# MagicWand_Schematic.net
KiCad netlist of a schematic drawn in Altium Designer
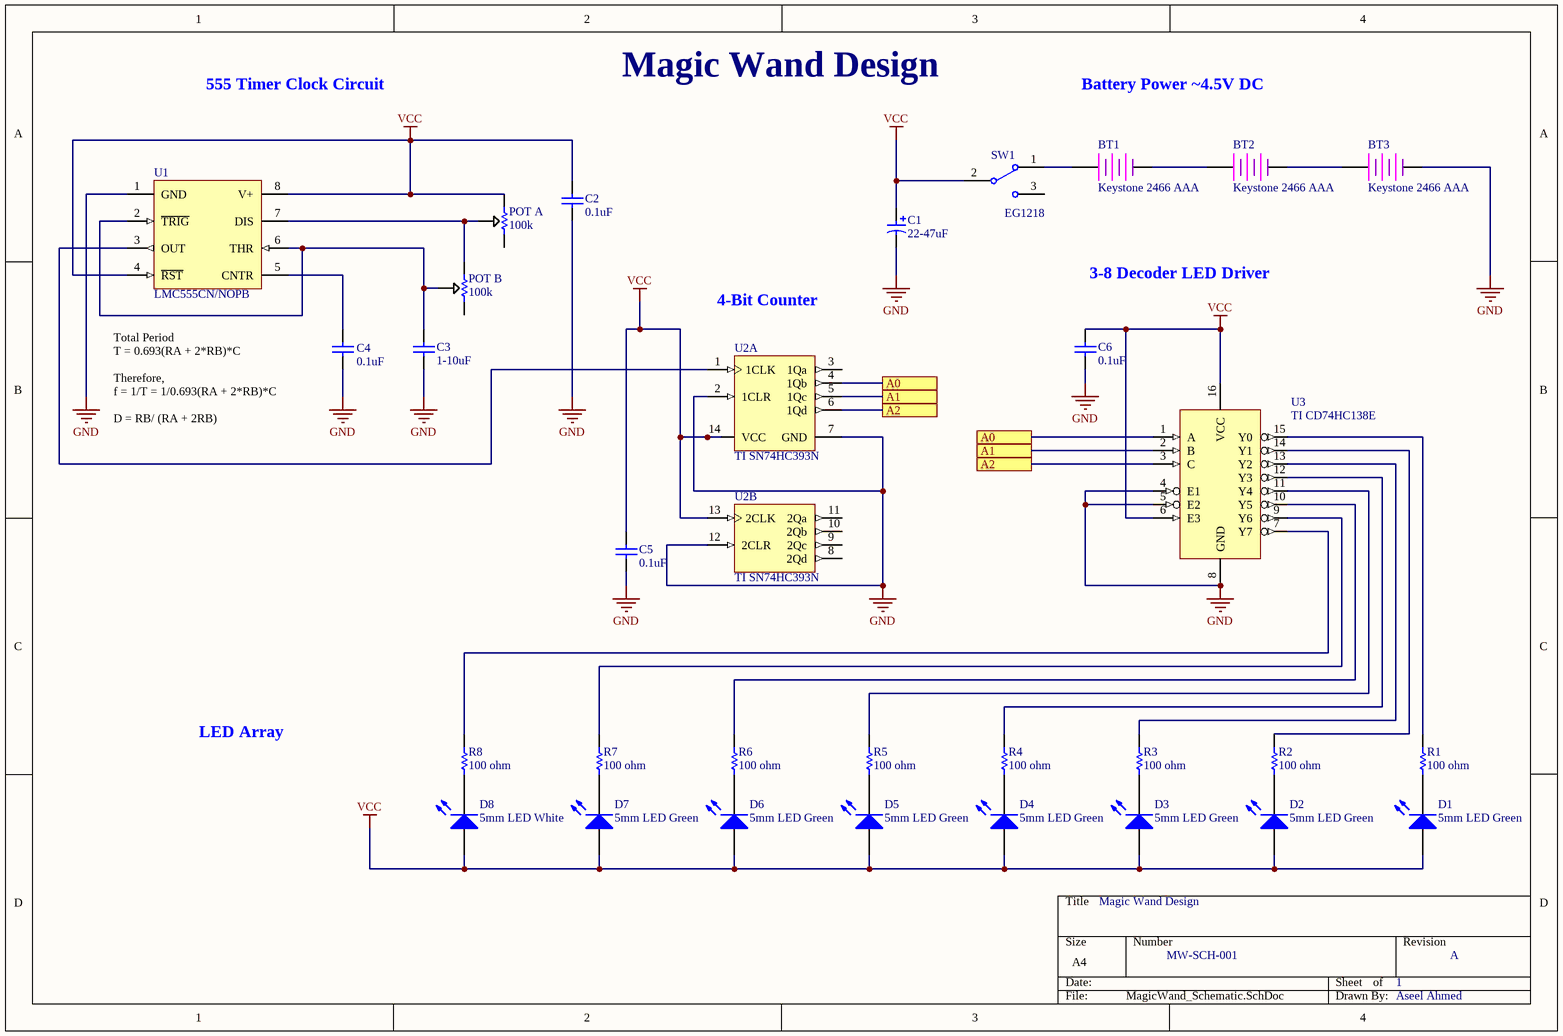
[diagram p0: MagicWand_Schematic.SchDoc]

(export (version "E")
  (design (tool "Eeschema 10.0.6"))
  (components
    (comp (ref "BT1")
      (value "Keystone 2466 AAA")
      (footprint "PCB-2466")
      (description "Battery holder, AAA, 1 cell, PC mount")
      (fields (field (name "MANUFACTURER PART NUMBER") "2466"))
      (libsource (lib "My Personal Space") (part "SYM-2466"))
    )
    (comp (ref "BT2")
      (value "Keystone 2466 AAA")
      (footprint "PCB-2466")
      (description "Battery holder, AAA, 1 cell, PC mount")
      (fields (field (name "MANUFACTURER PART NUMBER") "2466"))
      (libsource (lib "My Personal Space") (part "SYM-2466"))
    )
    (comp (ref "BT3")
      (value "Keystone 2466 AAA")
      (footprint "PCB-2466")
      (description "Battery holder, AAA, 1 cell, PC mount")
      (fields (field (name "MANUFACTURER PART NUMBER") "2466"))
      (libsource (lib "My Personal Space") (part "SYM-2466"))
    )
    (comp (ref "C1")
      (value "22-47uF")
      (footprint "PCB-xswzn1jk2ejoevwvaoxh-1")
      (description "Electrolytic capacitor Radial lead 2.5 mm 10 µF 16 V 20 % (Ø) 4 mm Panasonic EEA-GA1C100H 1 pc(s)")
      (libsource (lib "My Personal Space") (part "SYM-b868704b0d3c67af-1"))
    )
    (comp (ref "C2")
      (value "0.1uF")
      (footprint "PCB-ql28fbuo3tond8refhb5-1")
      (description "K 100nF Ceramic Multilayer Capacitor, 50 V dc, +125degC, X7R Dielectric, +/-10%")
      (libsource (lib "My Personal Space") (part "SYM-1272d9258f2acdb5-2"))
    )
    (comp (ref "C3")
      (value "1-10uF")
      (footprint "PCB-ql28fbuo3tond8refhb5-1")
      (description "K 100nF Ceramic Multilayer Capacitor, 50 V dc, +125degC, X7R Dielectric, +/-10%")
      (libsource (lib "My Personal Space") (part "SYM-1272d9258f2acdb5-2"))
    )
    (comp (ref "C4")
      (value "0.1uF")
      (footprint "PCB-ql28fbuo3tond8refhb5-1")
      (description "K 100nF Ceramic Multilayer Capacitor, 50 V dc, +125degC, X7R Dielectric, +/-10%")
      (libsource (lib "My Personal Space") (part "SYM-1272d9258f2acdb5-2"))
    )
    (comp (ref "C5")
      (value "0.1uF")
      (footprint "PCB-ql28fbuo3tond8refhb5-1")
      (description "K 100nF Ceramic Multilayer Capacitor, 50 V dc, +125degC, X7R Dielectric, +/-10%")
      (libsource (lib "My Personal Space") (part "SYM-1272d9258f2acdb5-2"))
    )
    (comp (ref "C6")
      (value "0.1uF")
      (footprint "PCB-ql28fbuo3tond8refhb5-1")
      (description "K 100nF Ceramic Multilayer Capacitor, 50 V dc, +125degC, X7R Dielectric, +/-10%")
      (libsource (lib "My Personal Space") (part "SYM-1272d9258f2acdb5-2"))
    )
    (comp (ref "D1")
      (value "5mm LED Green")
      (footprint "PCB-6hmn14p3euwrtpae4j9f-1")
      (description "Green 5 mm 60° Diffused 30 mcd 2.2 V Through Hole LED - T-1¾")
      (fields (field (name "MANUFACTURER PART NUMBER") "SSL-LX5093PGD"))
      (libsource (lib "My Personal Space") (part "SYM-4a898382afec954e-1"))
    )
    (comp (ref "D2")
      (value "5mm LED Green")
      (footprint "PCB-6hmn14p3euwrtpae4j9f-1")
      (description "Green 5 mm 60° Diffused 30 mcd 2.2 V Through Hole LED - T-1¾")
      (fields (field (name "MANUFACTURER PART NUMBER") "SSL-LX5093PGD"))
      (libsource (lib "My Personal Space") (part "SYM-4a898382afec954e-1"))
    )
    (comp (ref "D3")
      (value "5mm LED Green")
      (footprint "PCB-6hmn14p3euwrtpae4j9f-1")
      (description "Green 5 mm 60° Diffused 30 mcd 2.2 V Through Hole LED - T-1¾")
      (fields (field (name "MANUFACTURER PART NUMBER") "SSL-LX5093PGD"))
      (libsource (lib "My Personal Space") (part "SYM-4a898382afec954e-1"))
    )
    (comp (ref "D4")
      (value "5mm LED Green")
      (footprint "PCB-6hmn14p3euwrtpae4j9f-1")
      (description "Green 5 mm 60° Diffused 30 mcd 2.2 V Through Hole LED - T-1¾")
      (fields (field (name "MANUFACTURER PART NUMBER") "SSL-LX5093PGD"))
      (libsource (lib "My Personal Space") (part "SYM-4a898382afec954e-1"))
    )
    (comp (ref "D5")
      (value "5mm LED Green")
      (footprint "PCB-6hmn14p3euwrtpae4j9f-1")
      (description "Green 5 mm 60° Diffused 30 mcd 2.2 V Through Hole LED - T-1¾")
      (fields (field (name "MANUFACTURER PART NUMBER") "SSL-LX5093PGD"))
      (libsource (lib "My Personal Space") (part "SYM-4a898382afec954e-1"))
    )
    (comp (ref "D6")
      (value "5mm LED Green")
      (footprint "PCB-6hmn14p3euwrtpae4j9f-1")
      (description "Green 5 mm 60° Diffused 30 mcd 2.2 V Through Hole LED - T-1¾")
      (fields (field (name "MANUFACTURER PART NUMBER") "SSL-LX5093PGD"))
      (libsource (lib "My Personal Space") (part "SYM-4a898382afec954e-1"))
    )
    (comp (ref "D7")
      (value "5mm LED Green")
      (footprint "PCB-6hmn14p3euwrtpae4j9f-1")
      (description "Green 5 mm 60° Diffused 30 mcd 2.2 V Through Hole LED - T-1¾")
      (fields (field (name "MANUFACTURER PART NUMBER") "SSL-LX5093PGD"))
      (libsource (lib "My Personal Space") (part "SYM-4a898382afec954e-1"))
    )
    (comp (ref "D8")
      (value "5mm LED White")
      (footprint "PCB-6hmn14p3euwrtpae4j9f-1")
      (description "Green 5 mm 60° Diffused 30 mcd 2.2 V Through Hole LED - T-1¾")
      (fields (field (name "MANUFACTURER PART NUMBER") "SSL-LX5093PGD"))
      (libsource (lib "My Personal Space") (part "SYM-4a898382afec954e-1"))
    )
    (comp (ref "POT A")
      (value "100k")
      (footprint "PCB-1580288-1")
      (description "Res Cermet Trimmer 10K Ohm 10% 1/2W 1(Elec)/1(Mech)Turn 2.6mm (7 X 7 X 5.8mm) Pin Thru-Hole Bulk")
      (fields (field (name "MANUFACTURER PART NUMBER") "CT6EP103"))
      (libsource (lib "My Personal Space") (part "SYM-32ccf8683850ed0b-1"))
    )
    (comp (ref "POT B")
      (value "100k")
      (footprint "PCB-1580288-1")
      (description "Res Cermet Trimmer 10K Ohm 10% 1/2W 1(Elec)/1(Mech)Turn 2.6mm (7 X 7 X 5.8mm) Pin Thru-Hole Bulk")
      (fields (field (name "MANUFACTURER PART NUMBER") "CT6EP103"))
      (libsource (lib "My Personal Space") (part "SYM-32ccf8683850ed0b-1"))
    )
    (comp (ref "R1")
      (value "100 ohm")
      (footprint "PCB-0jk5y5qyb1smy9vf6b7t-1")
      (description "Res, 10K, 250mW, 5%, Axial")
      (libsource (lib "My Personal Space") (part "SYM-db3e1311f37e04f9-4"))
    )
    (comp (ref "R2")
      (value "100 ohm")
      (footprint "PCB-0jk5y5qyb1smy9vf6b7t-1")
      (description "Res, 10K, 250mW, 5%, Axial")
      (libsource (lib "My Personal Space") (part "SYM-db3e1311f37e04f9-4"))
    )
    (comp (ref "R3")
      (value "100 ohm")
      (footprint "PCB-0jk5y5qyb1smy9vf6b7t-1")
      (description "Res, 10K, 250mW, 5%, Axial")
      (libsource (lib "My Personal Space") (part "SYM-db3e1311f37e04f9-4"))
    )
    (comp (ref "R4")
      (value "100 ohm")
      (footprint "PCB-0jk5y5qyb1smy9vf6b7t-1")
      (description "Res, 10K, 250mW, 5%, Axial")
      (libsource (lib "My Personal Space") (part "SYM-db3e1311f37e04f9-4"))
    )
    (comp (ref "R5")
      (value "100 ohm")
      (footprint "PCB-0jk5y5qyb1smy9vf6b7t-1")
      (description "Res, 10K, 250mW, 5%, Axial")
      (libsource (lib "My Personal Space") (part "SYM-db3e1311f37e04f9-4"))
    )
    (comp (ref "R6")
      (value "100 ohm")
      (footprint "PCB-0jk5y5qyb1smy9vf6b7t-1")
      (description "Res, 10K, 250mW, 5%, Axial")
      (libsource (lib "My Personal Space") (part "SYM-db3e1311f37e04f9-4"))
    )
    (comp (ref "R7")
      (value "100 ohm")
      (footprint "PCB-0jk5y5qyb1smy9vf6b7t-1")
      (description "Res, 10K, 250mW, 5%, Axial")
      (libsource (lib "My Personal Space") (part "SYM-db3e1311f37e04f9-4"))
    )
    (comp (ref "R8")
      (value "100 ohm")
      (footprint "PCB-0jk5y5qyb1smy9vf6b7t-1")
      (description "Res, 10K, 250mW, 5%, Axial")
      (libsource (lib "My Personal Space") (part "SYM-db3e1311f37e04f9-4"))
    )
    (comp (ref "SW1")
      (value "EG1218")
      (footprint "ESWI-EG1218_V")
      (description "Slide Switch, 500 V, -20 to 70 degC, 3-Pin THD, RoHS")
      (libsource (lib "My Personal Space") (part "SW-SPDT-3"))
    )
    (comp (ref "U1")
      (value "LMC555CN/NOPB")
      (footprint "N08E")
      (description "CMOS Timer, 8-pin MDIP, Pb-Free")
      (libsource (lib "My Personal Space") (part "AN-TIMER-LMC555-8"))
    )
    (comp (ref "U2")
      (value "TI SN74HC393N")
      (footprint "PCB-te1ukpb7ypv15gwynu8x-1")
      (description "Texas Instruments - SN74HC393N - Counter/Divider Dual 4-Bit Binary UP 14-Pin PDIP Tube")
      (fields (field (name "MANUFACTURER PART NUMBER") "SN74HC393N"))
      (libsource (lib "My Personal Space") (part "SYM-3c53f5596157e394-2"))
    )
    (comp (ref "U3")
      (value "TI CD74HC138E")
      (footprint "PCB-iqyivjlmuk83cucpld0n-1")
      (description "TEXAS INSTRUMENTS   CD74HC138E   Logic Type:Decoder / Demultiplexer")
      (fields
        (field (name "MANUFACTURER") "Texas Instruments")
        (field (name "MANUFACTURER PART NUMBER") "CD74HC138E")
      )
      (libsource (lib "My Personal Space") (part "SYM-1166716-1"))
    )
  )
  (nets
    (net (code "1") (name "/A0") (class "Default")
      (node (ref "U2") (pin "4") (pinfunction "1Qb_4") (pintype "output"))
      (node (ref "U3") (pin "1") (pinfunction "A_1") (pintype "input"))
    )
    (net (code "2") (name "/A1") (class "Default")
      (node (ref "U2") (pin "5") (pinfunction "1Qc_5") (pintype "output"))
      (node (ref "U3") (pin "2") (pinfunction "B_2") (pintype "input"))
    )
    (net (code "3") (name "/A2") (class "Default")
      (node (ref "U2") (pin "6") (pinfunction "1Qd_6") (pintype "output"))
      (node (ref "U3") (pin "3") (pinfunction "C_3") (pintype "input"))
    )
    (net (code "4") (name "GND") (class "Default")
      (node (ref "BT3") (pin "2") (pinfunction "-_2") (pintype "passive"))
      (node (ref "C1") (pin "2") (pinfunction "2_2") (pintype "passive"))
      (node (ref "C2") (pin "1") (pinfunction "1_1") (pintype "passive"))
      (node (ref "C3") (pin "1") (pinfunction "1_1") (pintype "passive"))
      (node (ref "C4") (pin "1") (pinfunction "1_1") (pintype "passive"))
      (node (ref "C5") (pin "1") (pinfunction "1_1") (pintype "passive"))
      (node (ref "C6") (pin "1") (pinfunction "1_1") (pintype "passive"))
      (node (ref "U1") (pin "1") (pinfunction "GND_1") (pintype "power_in"))
      (node (ref "U2") (pin "12") (pinfunction "2CLR_12") (pintype "input"))
      (node (ref "U2") (pin "2") (pinfunction "1CLR_2") (pintype "input"))
      (node (ref "U2") (pin "7") (pinfunction "GND_7") (pintype "power_in"))
      (node (ref "U3") (pin "4") (pinfunction "E1_4") (pintype "input"))
      (node (ref "U3") (pin "5") (pinfunction "E2_5") (pintype "input"))
      (node (ref "U3") (pin "8") (pinfunction "GND_8") (pintype "power_in"))
    )
    (net (code "5") (name "Net-(BT1-+)") (class "Default")
      (node (ref "BT1") (pin "1") (pinfunction "+_1") (pintype "passive"))
      (node (ref "SW1") (pin "1") (pinfunction "1_1") (pintype "passive"))
    )
    (net (code "6") (name "Net-(BT1--)") (class "Default")
      (node (ref "BT1") (pin "2") (pinfunction "-_2") (pintype "passive"))
      (node (ref "BT2") (pin "1") (pinfunction "+_1") (pintype "passive"))
    )
    (net (code "7") (name "Net-(BT2--)") (class "Default")
      (node (ref "BT2") (pin "2") (pinfunction "-_2") (pintype "passive"))
      (node (ref "BT3") (pin "1") (pinfunction "+_1") (pintype "passive"))
    )
    (net (code "8") (name "Net-(D1-K)") (class "Default")
      (node (ref "D1") (pin "2") (pinfunction "K_2") (pintype "passive"))
      (node (ref "R1") (pin "1") (pinfunction "1_1") (pintype "passive"))
    )
    (net (code "9") (name "Net-(D2-K)") (class "Default")
      (node (ref "D2") (pin "2") (pinfunction "K_2") (pintype "passive"))
      (node (ref "R2") (pin "1") (pinfunction "1_1") (pintype "passive"))
    )
    (net (code "10") (name "Net-(D3-K)") (class "Default")
      (node (ref "D3") (pin "2") (pinfunction "K_2") (pintype "passive"))
      (node (ref "R3") (pin "1") (pinfunction "1_1") (pintype "passive"))
    )
    (net (code "11") (name "Net-(D4-K)") (class "Default")
      (node (ref "D4") (pin "2") (pinfunction "K_2") (pintype "passive"))
      (node (ref "R4") (pin "1") (pinfunction "1_1") (pintype "passive"))
    )
    (net (code "12") (name "Net-(D5-K)") (class "Default")
      (node (ref "D5") (pin "2") (pinfunction "K_2") (pintype "passive"))
      (node (ref "R5") (pin "1") (pinfunction "1_1") (pintype "passive"))
    )
    (net (code "13") (name "Net-(D6-K)") (class "Default")
      (node (ref "D6") (pin "2") (pinfunction "K_2") (pintype "passive"))
      (node (ref "R6") (pin "1") (pinfunction "1_1") (pintype "passive"))
    )
    (net (code "14") (name "Net-(D7-K)") (class "Default")
      (node (ref "D7") (pin "2") (pinfunction "K_2") (pintype "passive"))
      (node (ref "R7") (pin "1") (pinfunction "1_1") (pintype "passive"))
    )
    (net (code "15") (name "Net-(D8-K)") (class "Default")
      (node (ref "D8") (pin "2") (pinfunction "K_2") (pintype "passive"))
      (node (ref "R8") (pin "1") (pinfunction "1_1") (pintype "passive"))
    )
    (net (code "16") (name "Net-(U1-CNTR)") (class "Default")
      (node (ref "C4") (pin "2") (pinfunction "2_2") (pintype "passive"))
      (node (ref "U1") (pin "5") (pinfunction "CNTR_5") (pintype "passive"))
    )
    (net (code "17") (name "Net-(U1-DIS)") (class "Default")
      (node (ref "POT A") (pin "3") (pinfunction "3_3") (pintype "passive"))
      (node (ref "POT B") (pin "2") (pinfunction "2_2") (pintype "passive"))
      (node (ref "U1") (pin "7") (pinfunction "DIS_7") (pintype "open_collector"))
    )
    (net (code "18") (name "Net-(U1-OUT)") (class "Default")
      (node (ref "U1") (pin "3") (pinfunction "OUT_3") (pintype "output"))
      (node (ref "U2") (pin "1") (pinfunction "1CLK_1") (pintype "input"))
    )
    (net (code "19") (name "Net-(U1-THR)") (class "Default")
      (node (ref "C3") (pin "2") (pinfunction "2_2") (pintype "passive"))
      (node (ref "POT B") (pin "3") (pinfunction "3_3") (pintype "passive"))
      (node (ref "U1") (pin "2") (pinfunction "~{TRIG}_2") (pintype "input"))
      (node (ref "U1") (pin "6") (pinfunction "THR_6") (pintype "input"))
    )
    (net (code "20") (name "Net-(U3-Y0)") (class "Default")
      (node (ref "R1") (pin "2") (pinfunction "2_2") (pintype "passive"))
      (node (ref "U3") (pin "15") (pinfunction "Y0_15") (pintype "output"))
    )
    (net (code "21") (name "Net-(U3-Y1)") (class "Default")
      (node (ref "R2") (pin "2") (pinfunction "2_2") (pintype "passive"))
      (node (ref "U3") (pin "14") (pinfunction "Y1_14") (pintype "output"))
    )
    (net (code "22") (name "Net-(U3-Y2)") (class "Default")
      (node (ref "R3") (pin "2") (pinfunction "2_2") (pintype "passive"))
      (node (ref "U3") (pin "13") (pinfunction "Y2_13") (pintype "output"))
    )
    (net (code "23") (name "Net-(U3-Y3)") (class "Default")
      (node (ref "R4") (pin "2") (pinfunction "2_2") (pintype "passive"))
      (node (ref "U3") (pin "12") (pinfunction "Y3_12") (pintype "output"))
    )
    (net (code "24") (name "Net-(U3-Y4)") (class "Default")
      (node (ref "R5") (pin "2") (pinfunction "2_2") (pintype "passive"))
      (node (ref "U3") (pin "11") (pinfunction "Y4_11") (pintype "output"))
    )
    (net (code "25") (name "Net-(U3-Y5)") (class "Default")
      (node (ref "R6") (pin "2") (pinfunction "2_2") (pintype "passive"))
      (node (ref "U3") (pin "10") (pinfunction "Y5_10") (pintype "output"))
    )
    (net (code "26") (name "Net-(U3-Y6)") (class "Default")
      (node (ref "R7") (pin "2") (pinfunction "2_2") (pintype "passive"))
      (node (ref "U3") (pin "9") (pinfunction "Y6_9") (pintype "output"))
    )
    (net (code "27") (name "Net-(U3-Y7)") (class "Default")
      (node (ref "R8") (pin "2") (pinfunction "2_2") (pintype "passive"))
      (node (ref "U3") (pin "7") (pinfunction "Y7_7") (pintype "output"))
    )
    (net (code "28") (name "VCC") (class "Default")
      (node (ref "C1") (pin "1") (pinfunction "1_1") (pintype "passive"))
      (node (ref "C2") (pin "2") (pinfunction "2_2") (pintype "passive"))
      (node (ref "C5") (pin "2") (pinfunction "2_2") (pintype "passive"))
      (node (ref "C6") (pin "2") (pinfunction "2_2") (pintype "passive"))
      (node (ref "D1") (pin "1") (pinfunction "A_1") (pintype "passive"))
      (node (ref "D2") (pin "1") (pinfunction "A_1") (pintype "passive"))
      (node (ref "D3") (pin "1") (pinfunction "A_1") (pintype "passive"))
      (node (ref "D4") (pin "1") (pinfunction "A_1") (pintype "passive"))
      (node (ref "D5") (pin "1") (pinfunction "A_1") (pintype "passive"))
      (node (ref "D6") (pin "1") (pinfunction "A_1") (pintype "passive"))
      (node (ref "D7") (pin "1") (pinfunction "A_1") (pintype "passive"))
      (node (ref "D8") (pin "1") (pinfunction "A_1") (pintype "passive"))
      (node (ref "POT A") (pin "2") (pinfunction "2_2") (pintype "passive"))
      (node (ref "SW1") (pin "2") (pinfunction "COM_2") (pintype "passive"))
      (node (ref "U1") (pin "4") (pinfunction "~{RST}_4") (pintype "input"))
      (node (ref "U1") (pin "8") (pinfunction "V+_8") (pintype "power_in"))
      (node (ref "U2") (pin "13") (pinfunction "2CLK_13") (pintype "input"))
      (node (ref "U2") (pin "14") (pinfunction "VCC_14") (pintype "power_in"))
      (node (ref "U3") (pin "16") (pinfunction "VCC_16") (pintype "power_in"))
      (node (ref "U3") (pin "6") (pinfunction "E3_6") (pintype "input"))
    )
    (net (code "29") (name "unconnected-(POT A-Pad1)") (class "Default")
      (node (ref "POT A") (pin "1") (pinfunction "1_1") (pintype "passive"))
    )
    (net (code "30") (name "unconnected-(POT B-Pad1)") (class "Default")
      (node (ref "POT B") (pin "1") (pinfunction "1_1") (pintype "passive"))
    )
    (net (code "31") (name "unconnected-(SW1-Pad3)") (class "Default")
      (node (ref "SW1") (pin "3") (pinfunction "3_3") (pintype "passive"))
    )
    (net (code "32") (name "unconnected-(U2A-1Qa-Pad3)") (class "Default")
      (node (ref "U2") (pin "3") (pinfunction "1Qa_3") (pintype "output"))
    )
    (net (code "33") (name "unconnected-(U2B-2Qa-Pad11)") (class "Default")
      (node (ref "U2") (pin "11") (pinfunction "2Qa_11") (pintype "output"))
    )
    (net (code "34") (name "unconnected-(U2B-2Qb-Pad10)") (class "Default")
      (node (ref "U2") (pin "10") (pinfunction "2Qb_10") (pintype "output"))
    )
    (net (code "35") (name "unconnected-(U2B-2Qc-Pad9)") (class "Default")
      (node (ref "U2") (pin "9") (pinfunction "2Qc_9") (pintype "output"))
    )
    (net (code "36") (name "unconnected-(U2B-2Qd-Pad8)") (class "Default")
      (node (ref "U2") (pin "8") (pinfunction "2Qd_8") (pintype "output"))
    )
  )
)
